# Overview.net
KiCad netlist of a schematic drawn in Altium Designer
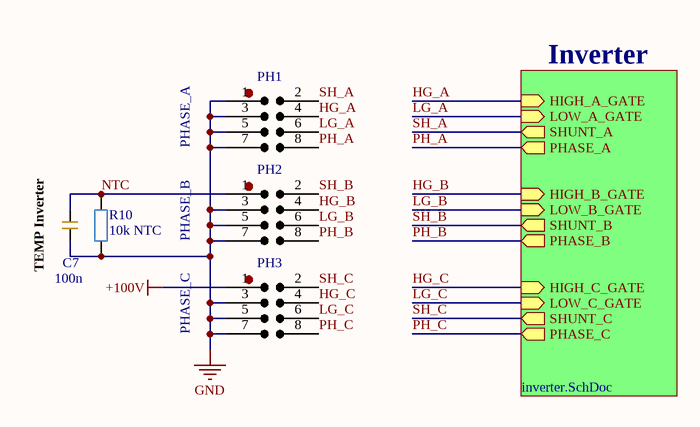
[diagram p0: Overview.SchDoc]

(export (version "E")
  (design (tool "Eeschema 10.0.6"))
  (components
    (comp (ref "C7")
      (value "100n")
      (footprint "CAP_0603")
      (description "Multilayer Ceramic Capacitors MLCC - SMD/SMT ROHS")
      (libsource (lib "Passive") (part "CAP_0603"))
    )
    (comp (ref "PH1")
      (value "PHASE_A")
      (footprint "PH_2x4_F")
      (fields (field (name "MFR.") "HCTL") (field (name "MFR. PART") "PM254-2-04-W-8.5"))
      (libsource (lib "Connectors") (part "PH_2x4_F"))
    )
    (comp (ref "PH2")
      (value "PHASE_B")
      (footprint "PH_2x4_F")
      (fields (field (name "MFR.") "HCTL") (field (name "MFR. PART") "PM254-2-04-W-8.5"))
      (libsource (lib "Connectors") (part "PH_2x4_F"))
    )
    (comp (ref "PH3")
      (value "PHASE_C")
      (footprint "PH_2x4_F")
      (fields (field (name "MFR.") "HCTL") (field (name "MFR. PART") "PM254-2-04-W-8.5"))
      (libsource (lib "Connectors") (part "PH_2x4_F"))
    )
    (comp (ref "R10")
      (value "10k NTC")
      (footprint "RES_0603")
      (description "100mW Thick Film Resistors")
      (libsource (lib "Passive") (part "RES_0603"))
    )
  )
  (nets
    (net (code "1") (name "+100V") (class "Default")
      (node (ref "PH3") (pin "1") (pinfunction "1_1") (pintype "passive"))
    )
    (net (code "2") (name "/HG_A") (class "Default")
      (node (ref "PH1") (pin "4") (pinfunction "4_4") (pintype "passive"))
    )
    (net (code "3") (name "/HG_B") (class "Default")
      (node (ref "PH2") (pin "4") (pinfunction "4_4") (pintype "passive"))
    )
    (net (code "4") (name "/HG_C") (class "Default")
      (node (ref "PH3") (pin "4") (pinfunction "4_4") (pintype "passive"))
    )
    (net (code "5") (name "/LG_A") (class "Default")
      (node (ref "PH1") (pin "6") (pinfunction "6_6") (pintype "passive"))
    )
    (net (code "6") (name "/LG_B") (class "Default")
      (node (ref "PH2") (pin "6") (pinfunction "6_6") (pintype "passive"))
    )
    (net (code "7") (name "/LG_C") (class "Default")
      (node (ref "PH3") (pin "6") (pinfunction "6_6") (pintype "passive"))
    )
    (net (code "8") (name "/NTC") (class "Default")
      (node (ref "C7") (pin "2") (pintype "passive"))
      (node (ref "PH2") (pin "1") (pinfunction "1_1") (pintype "passive"))
      (node (ref "R10") (pin "2") (pintype "passive"))
    )
    (net (code "9") (name "/PH_A") (class "Default")
      (node (ref "PH1") (pin "8") (pinfunction "8_8") (pintype "passive"))
    )
    (net (code "10") (name "/PH_B") (class "Default")
      (node (ref "PH2") (pin "8") (pinfunction "8_8") (pintype "passive"))
    )
    (net (code "11") (name "/PH_C") (class "Default")
      (node (ref "PH3") (pin "8") (pinfunction "8_8") (pintype "passive"))
    )
    (net (code "12") (name "/SH_A") (class "Default")
      (node (ref "PH1") (pin "2") (pinfunction "2_2") (pintype "passive"))
    )
    (net (code "13") (name "/SH_B") (class "Default")
      (node (ref "PH2") (pin "2") (pinfunction "2_2") (pintype "passive"))
    )
    (net (code "14") (name "/SH_C") (class "Default")
      (node (ref "PH3") (pin "2") (pinfunction "2_2") (pintype "passive"))
    )
    (net (code "15") (name "GND") (class "Default")
      (node (ref "C7") (pin "1") (pintype "passive"))
      (node (ref "PH1") (pin "1") (pinfunction "1_1") (pintype "passive"))
      (node (ref "PH1") (pin "3") (pinfunction "3_3") (pintype "passive"))
      (node (ref "PH1") (pin "5") (pinfunction "5_5") (pintype "passive"))
      (node (ref "PH1") (pin "7") (pinfunction "7_7") (pintype "passive"))
      (node (ref "PH2") (pin "3") (pinfunction "3_3") (pintype "passive"))
      (node (ref "PH2") (pin "5") (pinfunction "5_5") (pintype "passive"))
      (node (ref "PH2") (pin "7") (pinfunction "7_7") (pintype "passive"))
      (node (ref "PH3") (pin "3") (pinfunction "3_3") (pintype "passive"))
      (node (ref "PH3") (pin "5") (pinfunction "5_5") (pintype "passive"))
      (node (ref "PH3") (pin "7") (pinfunction "7_7") (pintype "passive"))
      (node (ref "R10") (pin "1") (pintype "passive"))
    )
  )
)
